# MCU2.net
KiCad netlist of a schematic drawn in Altium Designer
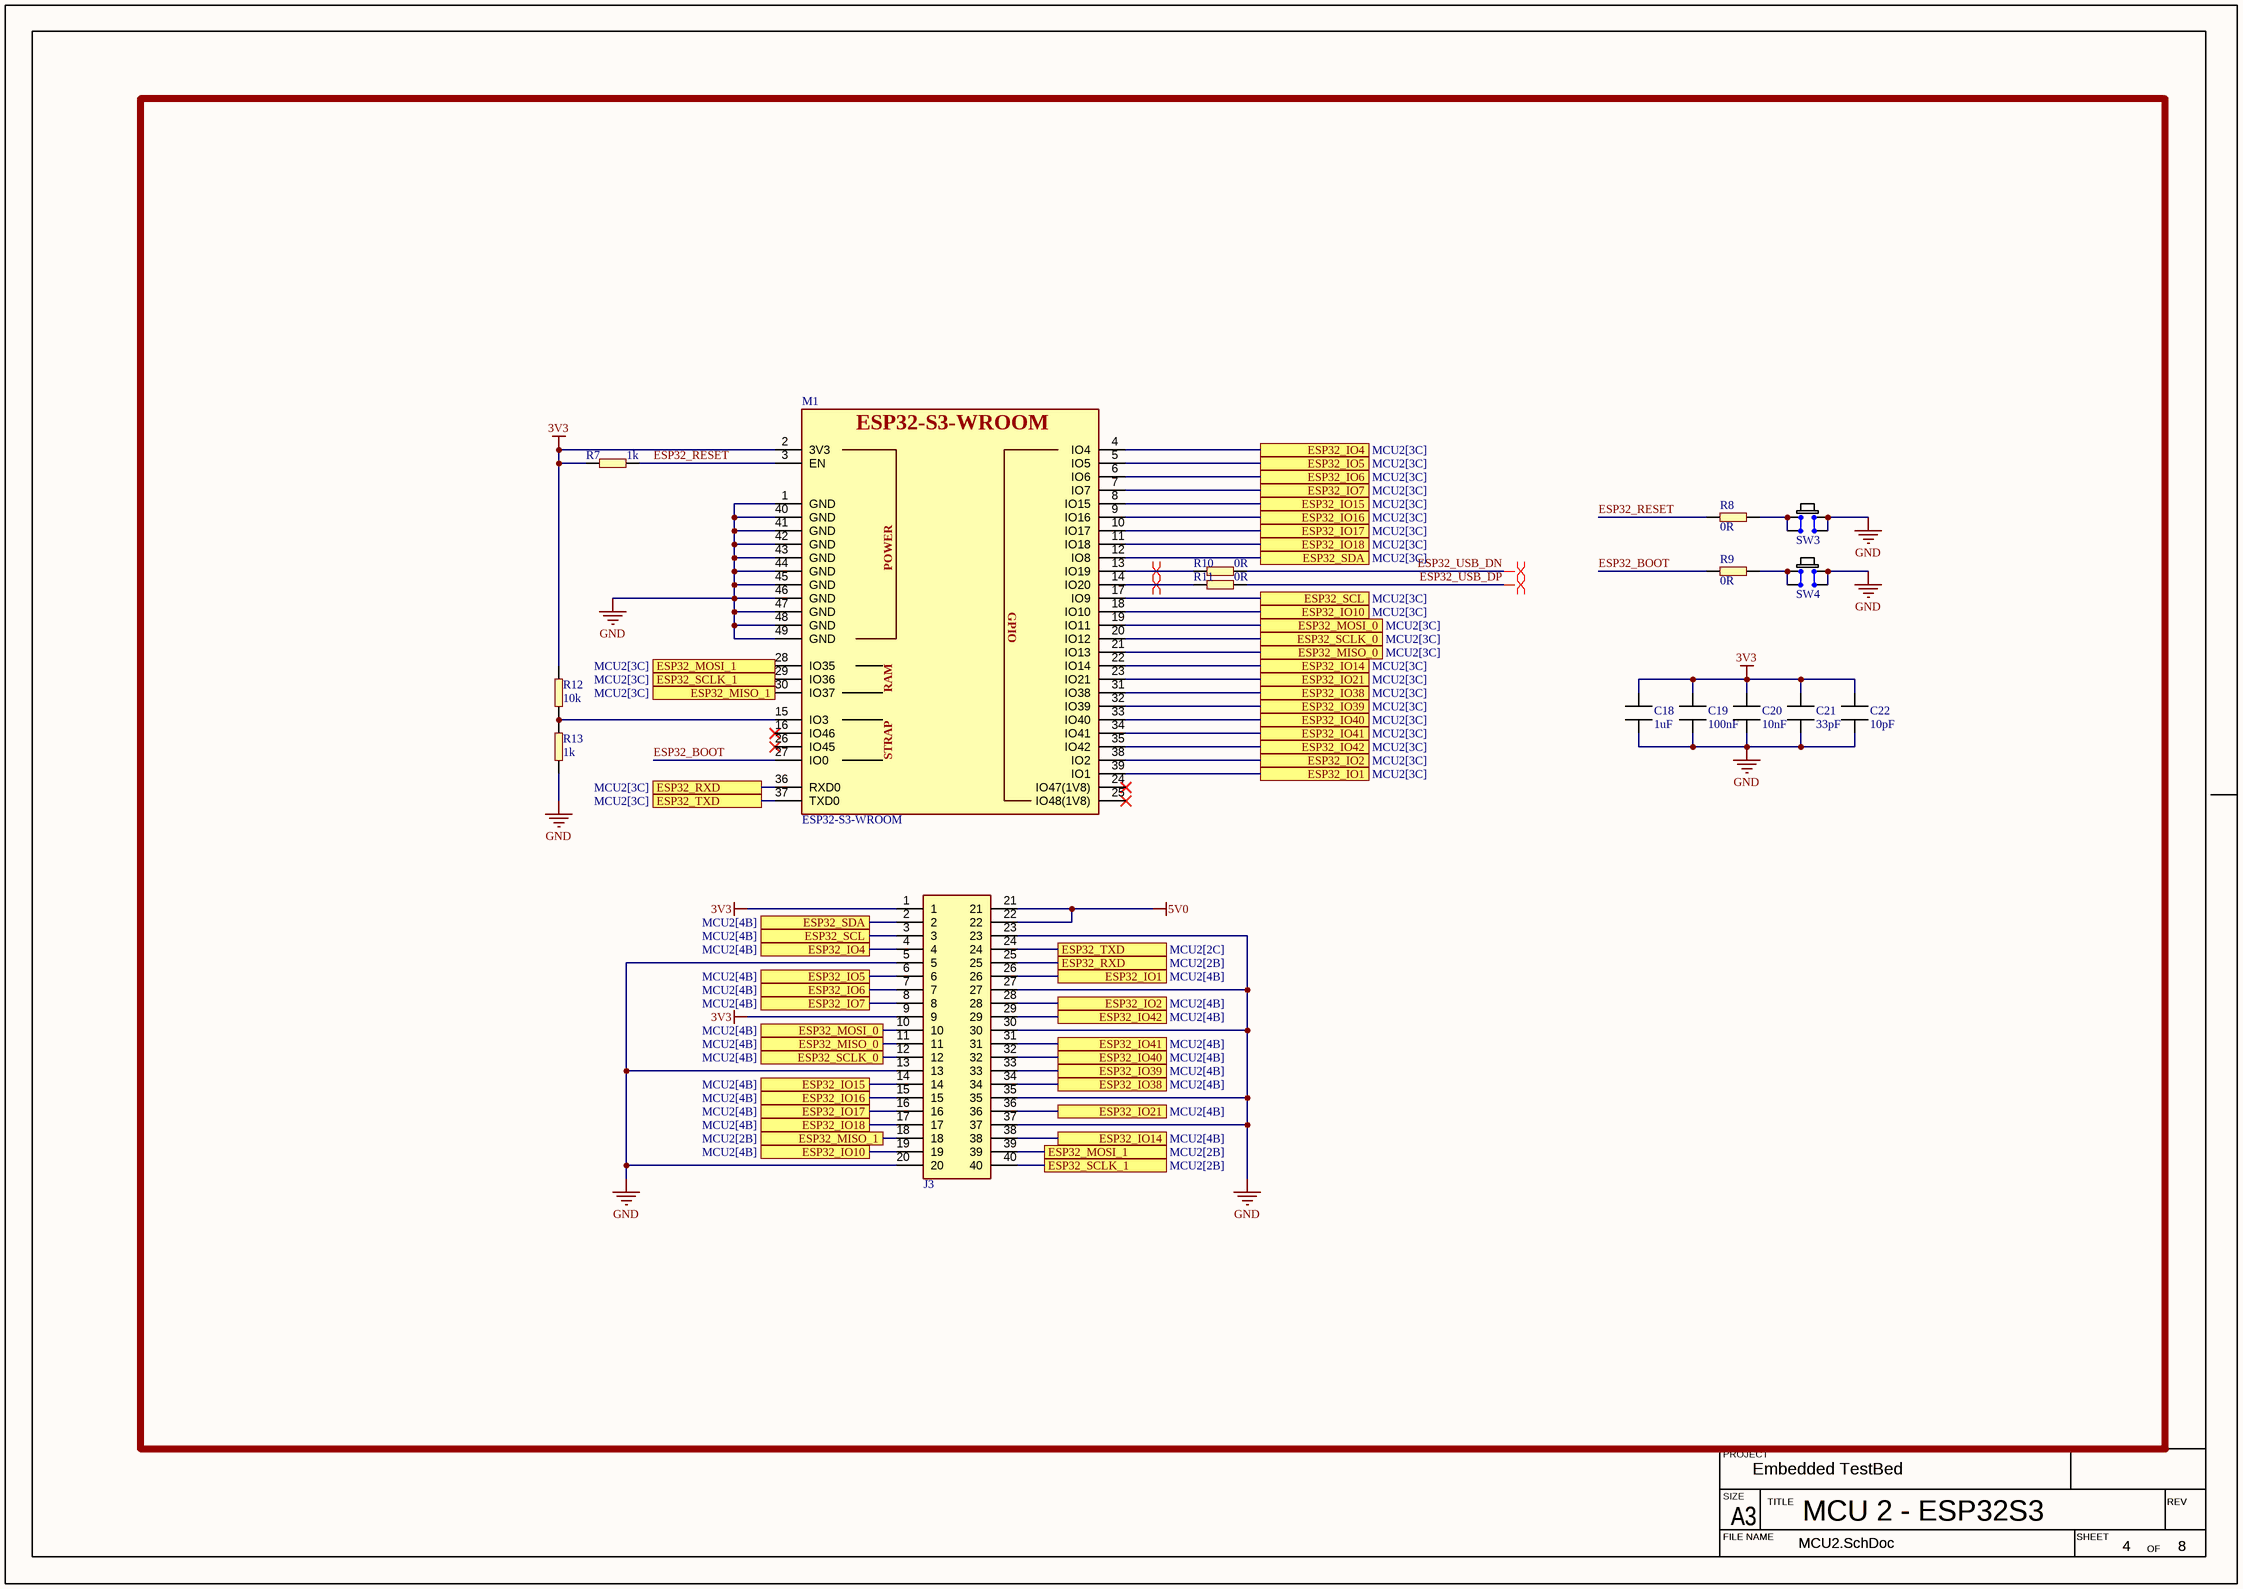
[diagram p0: MCU2.SchDoc]

(export (version "E")
  (design (tool "Eeschema 10.0.6"))
  (components
    (comp (ref "C18")
      (value "1uF")
      (footprint "CAPC2012X13L")
      (description "Chip Capacitor, 2-Leads, Body 2.00x1.25mm, IPC High Density")
      (fields (field (name "Comment") "MLCC_0805"))
      (libsource (lib "Capacitor") (part "MLCC_0805"))
    )
    (comp (ref "C19")
      (value "100nF")
      (footprint "CAPC2012X13L")
      (description "Chip Capacitor, 2-Leads, Body 2.00x1.25mm, IPC High Density")
      (fields (field (name "Comment") "MLCC_0805"))
      (libsource (lib "Capacitor") (part "MLCC_0805"))
    )
    (comp (ref "C20")
      (value "10nF")
      (footprint "CAPC2012X13L")
      (description "Chip Capacitor, 2-Leads, Body 2.00x1.25mm, IPC High Density")
      (fields (field (name "Comment") "MLCC_0805"))
      (libsource (lib "Capacitor") (part "MLCC_0805"))
    )
    (comp (ref "C21")
      (value "33pF")
      (footprint "CAPC2012X13L")
      (description "Chip Capacitor, 2-Leads, Body 2.00x1.25mm, IPC High Density")
      (fields (field (name "Comment") "MLCC_0805"))
      (libsource (lib "Capacitor") (part "MLCC_0805"))
    )
    (comp (ref "C22")
      (value "10pF")
      (footprint "CAPC2012X13L")
      (description "Chip Capacitor, 2-Leads, Body 2.00x1.25mm, IPC High Density")
      (fields (field (name "Comment") "MLCC_0805"))
      (libsource (lib "Capacitor") (part "MLCC_0805"))
    )
    (comp (ref "J3")
      (value "40PX2R_M_1")
      (footprint "40PX2R_Male_THT")
      (description "Berg Connector Header Through Hole  40 Position 0.100\" (2.54mm)")
      (libsource (lib "PinHeader") (part "40PX2R_M_1"))
    )
    (comp (ref "M1")
      (value "ESP32-S3-WROOM")
      (footprint "ESP32-S3-WROOM-1U")
      (description "ESP32-S3-WROOM Module")
      (libsource (lib "ESP") (part "ESP32-S3-WROOM"))
    )
    (comp (ref "R7")
      (value "1k")
      (footprint "RES_0805")
      (description "RES_0805")
      (fields (field (name "Comment") "ERP_101-1"))
      (libsource (lib "Resistor") (part "RES_0805"))
    )
    (comp (ref "R8")
      (value "0R")
      (footprint "RES_0805")
      (description "RES_0805")
      (fields (field (name "Comment") "ERP_101-1"))
      (libsource (lib "Resistor") (part "RES_0805"))
    )
    (comp (ref "R9")
      (value "0R")
      (footprint "RES_0805")
      (description "RES_0805")
      (fields (field (name "Comment") "ERP_101-1"))
      (libsource (lib "Resistor") (part "RES_0805"))
    )
    (comp (ref "R10")
      (value "0R")
      (footprint "RES_0805")
      (description "RES_0805")
      (fields (field (name "Comment") "ERP_101-1"))
      (libsource (lib "Resistor") (part "RES_0805"))
    )
    (comp (ref "R11")
      (value "0R")
      (footprint "RES_0805")
      (description "RES_0805")
      (fields (field (name "Comment") "ERP_101-1"))
      (libsource (lib "Resistor") (part "RES_0805"))
    )
    (comp (ref "R12")
      (value "10k")
      (footprint "RES_0805")
      (description "RES_0805")
      (fields (field (name "Comment") "ERP_101-1"))
      (libsource (lib "") (part "RES_0805_1"))
    )
    (comp (ref "R13")
      (value "1k")
      (footprint "RES_0805")
      (description "RES_0805")
      (fields (field (name "Comment") "ERP_101-1"))
      (libsource (lib "") (part "RES_0805_2"))
    )
    (comp (ref "SW3")
      (value "Generic6X6")
      (footprint "Generic6X6")
      (description "Tactile Switch SPST-NO Top Actuated Surface Mount")
      (libsource (lib "Switch") (part "Generic6X6"))
    )
    (comp (ref "SW4")
      (value "Generic6X6")
      (footprint "Generic6X6")
      (description "Tactile Switch SPST-NO Top Actuated Surface Mount")
      (libsource (lib "Switch") (part "Generic6X6"))
    )
  )
  (nets
    (net (code "1") (name "/ESP32_BOOT") (class "Default")
      (node (ref "M1") (pin "27") (pinfunction "IO0_27") (pintype "passive"))
      (node (ref "R9") (pin "2") (pinfunction "2_2") (pintype "passive"))
    )
    (net (code "2") (name "/ESP32_IO1") (class "Default")
      (node (ref "J3") (pin "26") (pinfunction "26_26") (pintype "passive"))
      (node (ref "M1") (pin "39") (pinfunction "IO1_39") (pintype "passive"))
    )
    (net (code "3") (name "/ESP32_IO2") (class "Default")
      (node (ref "J3") (pin "28") (pinfunction "28_28") (pintype "passive"))
      (node (ref "M1") (pin "38") (pinfunction "IO2_38") (pintype "passive"))
    )
    (net (code "4") (name "/ESP32_IO4") (class "Default")
      (node (ref "J3") (pin "4") (pinfunction "4_4") (pintype "passive"))
      (node (ref "M1") (pin "4") (pinfunction "IO4_4") (pintype "passive"))
    )
    (net (code "5") (name "/ESP32_IO5") (class "Default")
      (node (ref "J3") (pin "6") (pinfunction "6_6") (pintype "passive"))
      (node (ref "M1") (pin "5") (pinfunction "IO5_5") (pintype "passive"))
    )
    (net (code "6") (name "/ESP32_IO6") (class "Default")
      (node (ref "J3") (pin "7") (pinfunction "7_7") (pintype "passive"))
      (node (ref "M1") (pin "6") (pinfunction "IO6_6") (pintype "passive"))
    )
    (net (code "7") (name "/ESP32_IO7") (class "Default")
      (node (ref "J3") (pin "8") (pinfunction "8_8") (pintype "passive"))
      (node (ref "M1") (pin "7") (pinfunction "IO7_7") (pintype "passive"))
    )
    (net (code "8") (name "/ESP32_IO10") (class "Default")
      (node (ref "J3") (pin "19") (pinfunction "19_19") (pintype "passive"))
      (node (ref "M1") (pin "18") (pinfunction "IO10_18") (pintype "passive"))
    )
    (net (code "9") (name "/ESP32_IO14") (class "Default")
      (node (ref "J3") (pin "38") (pinfunction "38_38") (pintype "passive"))
      (node (ref "M1") (pin "22") (pinfunction "IO14_22") (pintype "passive"))
    )
    (net (code "10") (name "/ESP32_IO15") (class "Default")
      (node (ref "J3") (pin "14") (pinfunction "14_14") (pintype "passive"))
      (node (ref "M1") (pin "8") (pinfunction "IO15_8") (pintype "passive"))
    )
    (net (code "11") (name "/ESP32_IO16") (class "Default")
      (node (ref "J3") (pin "15") (pinfunction "15_15") (pintype "passive"))
      (node (ref "M1") (pin "9") (pinfunction "IO16_9") (pintype "passive"))
    )
    (net (code "12") (name "/ESP32_IO17") (class "Default")
      (node (ref "J3") (pin "16") (pinfunction "16_16") (pintype "passive"))
      (node (ref "M1") (pin "10") (pinfunction "IO17_10") (pintype "passive"))
    )
    (net (code "13") (name "/ESP32_IO18") (class "Default")
      (node (ref "J3") (pin "17") (pinfunction "17_17") (pintype "passive"))
      (node (ref "M1") (pin "11") (pinfunction "IO18_11") (pintype "passive"))
    )
    (net (code "14") (name "/ESP32_IO21") (class "Default")
      (node (ref "J3") (pin "36") (pinfunction "36_36") (pintype "passive"))
      (node (ref "M1") (pin "23") (pinfunction "IO21_23") (pintype "passive"))
    )
    (net (code "15") (name "/ESP32_IO38") (class "Default")
      (node (ref "J3") (pin "34") (pinfunction "34_34") (pintype "passive"))
      (node (ref "M1") (pin "31") (pinfunction "IO38_31") (pintype "passive"))
    )
    (net (code "16") (name "/ESP32_IO39") (class "Default")
      (node (ref "J3") (pin "33") (pinfunction "33_33") (pintype "passive"))
      (node (ref "M1") (pin "32") (pinfunction "IO39_32") (pintype "passive"))
    )
    (net (code "17") (name "/ESP32_IO40") (class "Default")
      (node (ref "J3") (pin "32") (pinfunction "32_32") (pintype "passive"))
      (node (ref "M1") (pin "33") (pinfunction "IO40_33") (pintype "passive"))
    )
    (net (code "18") (name "/ESP32_IO41") (class "Default")
      (node (ref "J3") (pin "31") (pinfunction "31_31") (pintype "passive"))
      (node (ref "M1") (pin "34") (pinfunction "IO41_34") (pintype "passive"))
    )
    (net (code "19") (name "/ESP32_IO42") (class "Default")
      (node (ref "J3") (pin "29") (pinfunction "29_29") (pintype "passive"))
      (node (ref "M1") (pin "35") (pinfunction "IO42_35") (pintype "passive"))
    )
    (net (code "20") (name "/ESP32_MISO_0") (class "Default")
      (node (ref "J3") (pin "11") (pinfunction "11_11") (pintype "passive"))
      (node (ref "M1") (pin "21") (pinfunction "IO13_21") (pintype "passive"))
    )
    (net (code "21") (name "/ESP32_MISO_1") (class "Default")
      (node (ref "J3") (pin "18") (pinfunction "18_18") (pintype "passive"))
      (node (ref "M1") (pin "30") (pinfunction "IO37_30") (pintype "passive"))
    )
    (net (code "22") (name "/ESP32_MOSI_0") (class "Default")
      (node (ref "J3") (pin "10") (pinfunction "10_10") (pintype "passive"))
      (node (ref "M1") (pin "19") (pinfunction "IO11_19") (pintype "passive"))
    )
    (net (code "23") (name "/ESP32_MOSI_1") (class "Default")
      (node (ref "J3") (pin "39") (pinfunction "39_39") (pintype "passive"))
      (node (ref "M1") (pin "28") (pinfunction "IO35_28") (pintype "passive"))
    )
    (net (code "24") (name "/ESP32_RESET") (class "Default")
      (node (ref "M1") (pin "3") (pinfunction "EN_3") (pintype "passive"))
      (node (ref "R7") (pin "1") (pinfunction "1_1") (pintype "passive"))
      (node (ref "R8") (pin "2") (pinfunction "2_2") (pintype "passive"))
    )
    (net (code "25") (name "/ESP32_RXD") (class "Default")
      (node (ref "J3") (pin "25") (pinfunction "25_25") (pintype "passive"))
      (node (ref "M1") (pin "36") (pinfunction "RXD0_36") (pintype "passive"))
    )
    (net (code "26") (name "/ESP32_SCL") (class "Default")
      (node (ref "J3") (pin "3") (pinfunction "3_3") (pintype "passive"))
      (node (ref "M1") (pin "17") (pinfunction "IO9_17") (pintype "passive"))
    )
    (net (code "27") (name "/ESP32_SCLK_0") (class "Default")
      (node (ref "J3") (pin "12") (pinfunction "12_12") (pintype "passive"))
      (node (ref "M1") (pin "20") (pinfunction "IO12_20") (pintype "passive"))
    )
    (net (code "28") (name "/ESP32_SCLK_1") (class "Default")
      (node (ref "J3") (pin "40") (pinfunction "40_40") (pintype "passive"))
      (node (ref "M1") (pin "29") (pinfunction "IO36_29") (pintype "passive"))
    )
    (net (code "29") (name "/ESP32_SDA") (class "Default")
      (node (ref "J3") (pin "2") (pinfunction "2_2") (pintype "passive"))
      (node (ref "M1") (pin "12") (pinfunction "IO8_12") (pintype "passive"))
    )
    (net (code "30") (name "/ESP32_TXD") (class "Default")
      (node (ref "J3") (pin "24") (pinfunction "24_24") (pintype "passive"))
      (node (ref "M1") (pin "37") (pinfunction "TXD0_37") (pintype "passive"))
    )
    (net (code "31") (name "/ESP32_USB_DN") (class "Default")
      (node (ref "R10") (pin "1") (pinfunction "1_1") (pintype "passive"))
    )
    (net (code "32") (name "/ESP32_USB_DP") (class "Default")
      (node (ref "R11") (pin "1") (pinfunction "1_1") (pintype "passive"))
    )
    (net (code "33") (name "3V3") (class "Default")
      (node (ref "C18") (pin "1") (pinfunction "1_1") (pintype "passive"))
      (node (ref "C19") (pin "1") (pinfunction "1_1") (pintype "passive"))
      (node (ref "C20") (pin "1") (pinfunction "1_1") (pintype "passive"))
      (node (ref "C21") (pin "1") (pinfunction "1_1") (pintype "passive"))
      (node (ref "C22") (pin "1") (pinfunction "1_1") (pintype "passive"))
      (node (ref "J3") (pin "1") (pinfunction "1_1") (pintype "passive"))
      (node (ref "J3") (pin "9") (pinfunction "9_9") (pintype "passive"))
      (node (ref "M1") (pin "2") (pinfunction "3V3_2") (pintype "passive"))
      (node (ref "R12") (pin "2") (pinfunction "2_2") (pintype "passive"))
      (node (ref "R7") (pin "2") (pinfunction "2_2") (pintype "passive"))
    )
    (net (code "34") (name "5V0") (class "Default")
      (node (ref "J3") (pin "21") (pinfunction "21_21") (pintype "passive"))
      (node (ref "J3") (pin "22") (pinfunction "22_22") (pintype "passive"))
    )
    (net (code "35") (name "GND") (class "Default")
      (node (ref "C18") (pin "2") (pinfunction "2_2") (pintype "passive"))
      (node (ref "C19") (pin "2") (pinfunction "2_2") (pintype "passive"))
      (node (ref "C20") (pin "2") (pinfunction "2_2") (pintype "passive"))
      (node (ref "C21") (pin "2") (pinfunction "2_2") (pintype "passive"))
      (node (ref "C22") (pin "2") (pinfunction "2_2") (pintype "passive"))
      (node (ref "J3") (pin "13") (pinfunction "13_13") (pintype "passive"))
      (node (ref "J3") (pin "20") (pinfunction "20_20") (pintype "passive"))
      (node (ref "J3") (pin "23") (pinfunction "23_23") (pintype "passive"))
      (node (ref "J3") (pin "27") (pinfunction "27_27") (pintype "passive"))
      (node (ref "J3") (pin "30") (pinfunction "30_30") (pintype "passive"))
      (node (ref "J3") (pin "35") (pinfunction "35_35") (pintype "passive"))
      (node (ref "J3") (pin "37") (pinfunction "37_37") (pintype "passive"))
      (node (ref "J3") (pin "5") (pinfunction "5_5") (pintype "passive"))
      (node (ref "M1") (pin "1") (pinfunction "GND_1") (pintype "power_in"))
      (node (ref "M1") (pin "40") (pinfunction "GND_40") (pintype "power_in"))
      (node (ref "M1") (pin "41") (pinfunction "GND_41") (pintype "power_in"))
      (node (ref "M1") (pin "42") (pinfunction "GND_42") (pintype "power_in"))
      (node (ref "M1") (pin "43") (pinfunction "GND_43") (pintype "power_in"))
      (node (ref "M1") (pin "44") (pinfunction "GND_44") (pintype "power_in"))
      (node (ref "M1") (pin "45") (pinfunction "GND_45") (pintype "power_in"))
      (node (ref "M1") (pin "46") (pinfunction "GND_46") (pintype "power_in"))
      (node (ref "M1") (pin "47") (pinfunction "GND_47") (pintype "power_in"))
      (node (ref "M1") (pin "48") (pinfunction "GND_48") (pintype "power_in"))
      (node (ref "M1") (pin "49") (pinfunction "GND_49") (pintype "power_in"))
      (node (ref "R13") (pin "2") (pinfunction "2_2") (pintype "passive"))
      (node (ref "SW3") (pin "3") (pinfunction "COM_3") (pintype "passive"))
      (node (ref "SW3") (pin "4") (pinfunction "COM_4") (pintype "passive"))
      (node (ref "SW4") (pin "3") (pinfunction "COM_3") (pintype "passive"))
      (node (ref "SW4") (pin "4") (pinfunction "COM_4") (pintype "passive"))
    )
    (net (code "36") (name "Net-(M1-IO3)") (class "Default")
      (node (ref "M1") (pin "15") (pinfunction "IO3_15") (pintype "passive"))
      (node (ref "R12") (pin "1") (pinfunction "1_1") (pintype "passive"))
      (node (ref "R13") (pin "1") (pinfunction "1_1") (pintype "passive"))
    )
    (net (code "37") (name "Net-(M1-IO19)") (class "Default")
      (node (ref "M1") (pin "13") (pinfunction "IO19_13") (pintype "passive"))
      (node (ref "R10") (pin "2") (pinfunction "2_2") (pintype "passive"))
    )
    (net (code "38") (name "Net-(M1-IO20)") (class "Default")
      (node (ref "M1") (pin "14") (pinfunction "IO20_14") (pintype "passive"))
      (node (ref "R11") (pin "2") (pinfunction "2_2") (pintype "passive"))
    )
    (net (code "39") (name "Net-(R8-Pad1)") (class "Default")
      (node (ref "R8") (pin "1") (pinfunction "1_1") (pintype "passive"))
      (node (ref "SW3") (pin "1") (pinfunction "NO_1") (pintype "passive"))
      (node (ref "SW3") (pin "2") (pinfunction "NO_2") (pintype "passive"))
    )
    (net (code "40") (name "Net-(R9-Pad1)") (class "Default")
      (node (ref "R9") (pin "1") (pinfunction "1_1") (pintype "passive"))
      (node (ref "SW4") (pin "1") (pinfunction "NO_1") (pintype "passive"))
      (node (ref "SW4") (pin "2") (pinfunction "NO_2") (pintype "passive"))
    )
    (net (code "41") (name "unconnected-(M1-IO45-Pad26)") (class "Default")
      (node (ref "M1") (pin "26") (pinfunction "IO45_26") (pintype "passive+no_connect"))
    )
    (net (code "42") (name "unconnected-(M1-IO46-Pad16)") (class "Default")
      (node (ref "M1") (pin "16") (pinfunction "IO46_16") (pintype "passive+no_connect"))
    )
    (net (code "43") (name "unconnected-(M1-IO47(1V8)-Pad24)") (class "Default")
      (node (ref "M1") (pin "24") (pinfunction "IO47(1V8)_24") (pintype "passive+no_connect"))
    )
    (net (code "44") (name "unconnected-(M1-IO48(1V8)-Pad25)") (class "Default")
      (node (ref "M1") (pin "25") (pinfunction "IO48(1V8)_25") (pintype "passive+no_connect"))
    )
  )
)
